# design.net
KiCad netlist of a schematic drawn in Altium Designer
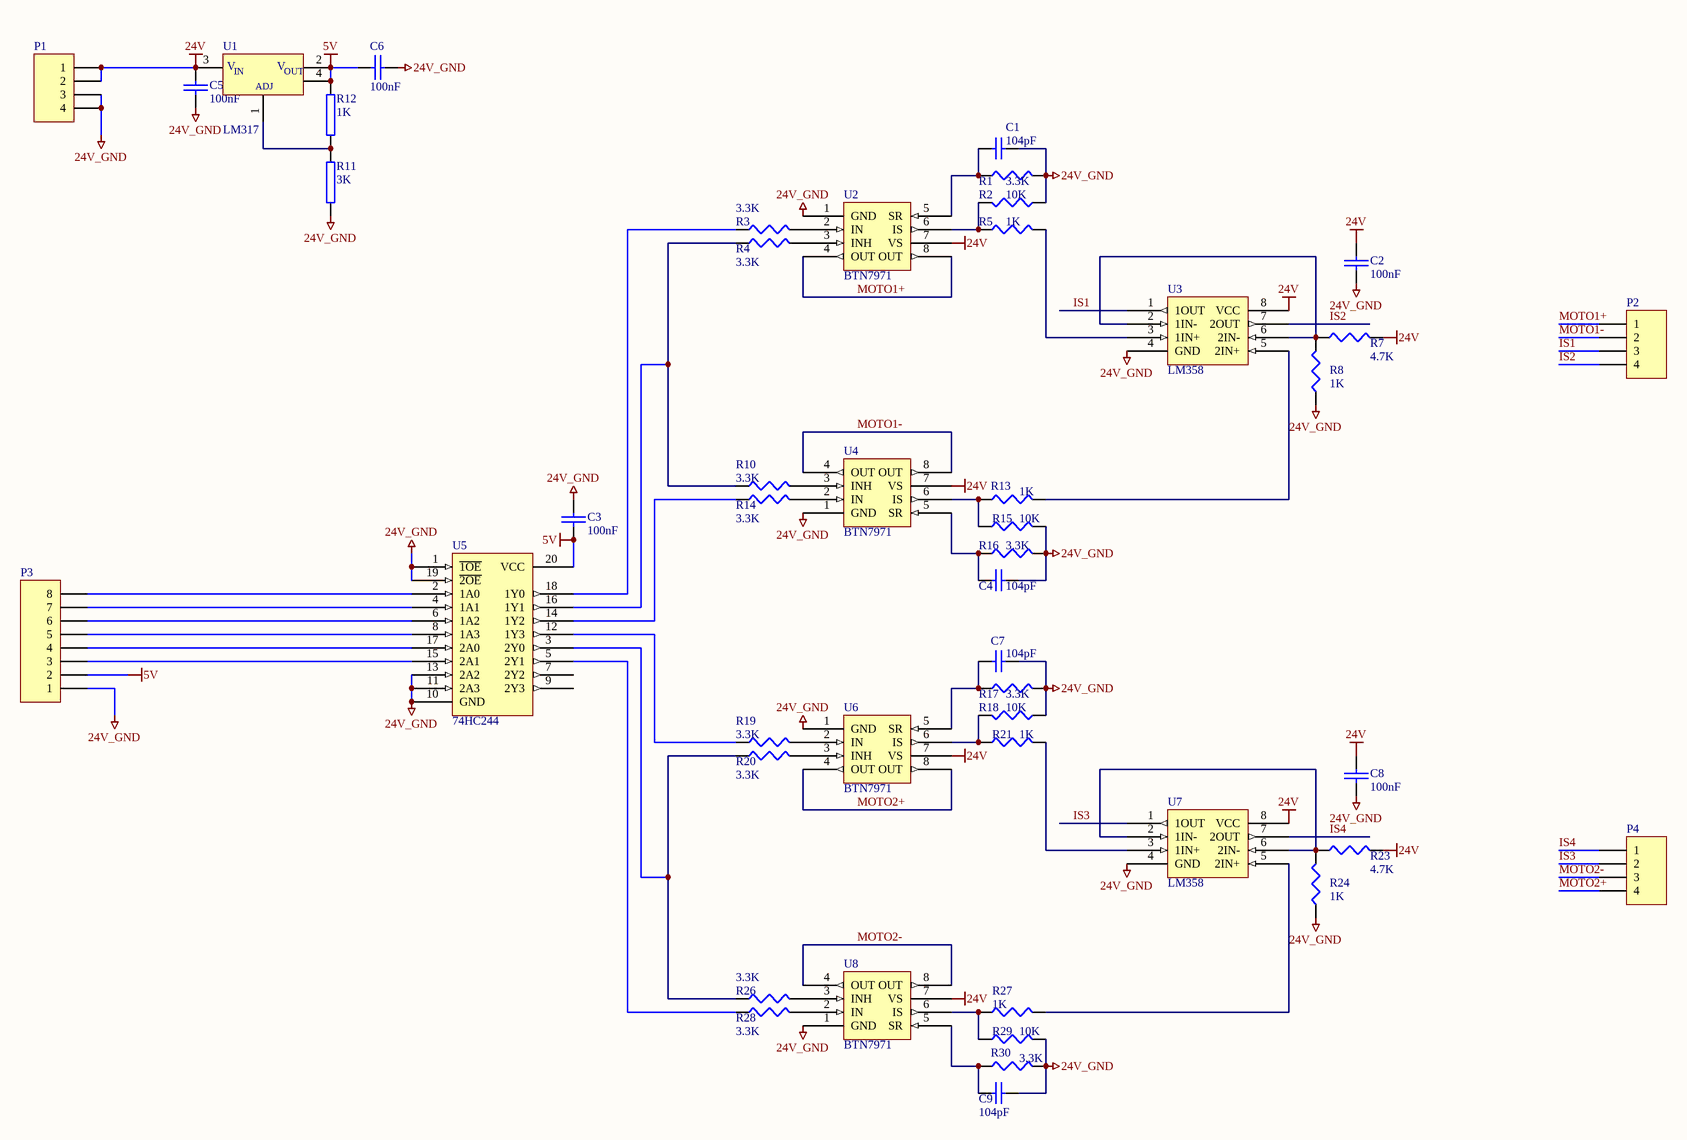
[diagram p0: 双电机电机模块.SchDoc]

(export (version "E")
  (design (tool "Eeschema 10.0.6"))
  (components
    (comp (ref "C1")
      (value "104pF")
      (footprint "0603c")
      (description "Capacitor (Semiconductor SIM Model)")
      (fields (field (name "Comment") "Cap Semi") (field (name "PUBLISHER") "Altium Limited"))
      (libsource (lib "Miscellaneous Devices") (part "Cap Semi"))
    )
    (comp (ref "C2")
      (value "100nF")
      (footprint "0603C")
      (description "CAP")
      (libsource (lib "*") (part "CAP"))
    )
    (comp (ref "C3")
      (value "100nF")
      (footprint "0603C")
      (description "CAP")
      (libsource (lib "*") (part "CAP"))
    )
    (comp (ref "C4")
      (value "104pF")
      (footprint "0603c")
      (description "Capacitor (Semiconductor SIM Model)")
      (fields (field (name "Comment") "Cap Semi") (field (name "PUBLISHER") "Altium Limited"))
      (libsource (lib "Miscellaneous Devices") (part "Cap Semi"))
    )
    (comp (ref "C5")
      (value "100nF")
      (footprint "0603C")
      (description "CAP")
      (libsource (lib "*") (part "CAP"))
    )
    (comp (ref "C6")
      (value "100nF")
      (footprint "0603C")
      (description "CAP")
      (libsource (lib "*") (part "CAP"))
    )
    (comp (ref "C7")
      (value "104pF")
      (footprint "0603c")
      (description "Capacitor (Semiconductor SIM Model)")
      (fields (field (name "Comment") "Cap Semi") (field (name "PUBLISHER") "Altium Limited"))
      (libsource (lib "Miscellaneous Devices") (part "Cap Semi"))
    )
    (comp (ref "C8")
      (value "100nF")
      (footprint "0603C")
      (description "CAP")
      (libsource (lib "*") (part "CAP"))
    )
    (comp (ref "C9")
      (value "104pF")
      (footprint "0603c")
      (description "Capacitor (Semiconductor SIM Model)")
      (fields (field (name "Comment") "Cap Semi") (field (name "PUBLISHER") "Altium Limited"))
      (libsource (lib "Miscellaneous Devices") (part "Cap Semi"))
    )
    (comp (ref "P1")
      (value "~")
      (footprint "4ELPV-3.96")
      (description "Header, 4-Pin")
      (fields (field (name "PUBLISHER") "Altium Limited"))
      (libsource (lib "") (part "Header 4_1"))
    )
    (comp (ref "P2")
      (value "~")
      (footprint "4ELPV-3.96")
      (description "Header, 4-Pin")
      (fields (field (name "PUBLISHER") "Altium Limited"))
      (libsource (lib "Miscellaneous Connectors") (part "Header 4"))
    )
    (comp (ref "P3")
      (value "~")
      (footprint "HDR1X8")
      (description "Header, 8-Pin")
      (fields (field (name "PUBLISHER") "Altium Limited"))
      (libsource (lib "Miscellaneous Connectors") (part "Header 8"))
    )
    (comp (ref "P4")
      (value "~")
      (footprint "4ELPV-3.96")
      (description "Header, 4-Pin")
      (fields (field (name "PUBLISHER") "Altium Limited"))
      (libsource (lib "Miscellaneous Connectors") (part "Header 4"))
    )
    (comp (ref "R1")
      (value "3.3K")
      (footprint "0603R")
      (description "Resistor")
      (fields (field (name "Comment") "Res3") (field (name "PUBLISHER") "Altium Limited"))
      (libsource (lib "Miscellaneous Devices") (part "Res3"))
    )
    (comp (ref "R2")
      (value "10K")
      (footprint "0603R")
      (description "Resistor")
      (fields (field (name "Comment") "Res3") (field (name "PUBLISHER") "Altium Limited"))
      (libsource (lib "Miscellaneous Devices") (part "Res3"))
    )
    (comp (ref "R3")
      (value "3.3K")
      (footprint "0603R")
      (description "Resistor")
      (fields (field (name "Comment") "Res3") (field (name "PUBLISHER") "Altium Limited"))
      (libsource (lib "Miscellaneous Devices") (part "Res3"))
    )
    (comp (ref "R4")
      (value "3.3K")
      (footprint "0603R")
      (description "Resistor")
      (fields (field (name "Comment") "Res3") (field (name "PUBLISHER") "Altium Limited"))
      (libsource (lib "Miscellaneous Devices") (part "Res3"))
    )
    (comp (ref "R5")
      (value "1K")
      (footprint "0603R")
      (description "Resistor")
      (fields (field (name "Comment") "Res3") (field (name "PUBLISHER") "Altium Limited"))
      (libsource (lib "Miscellaneous Devices") (part "Res3"))
    )
    (comp (ref "R7")
      (value "4.7K")
      (footprint "0603R")
      (description "Resistor")
      (fields (field (name "Comment") "Res3") (field (name "PUBLISHER") "Altium Limited"))
      (libsource (lib "Miscellaneous Devices") (part "Res3"))
    )
    (comp (ref "R8")
      (value "1K")
      (footprint "0603R")
      (description "Resistor")
      (fields (field (name "Comment") "Res3") (field (name "PUBLISHER") "Altium Limited"))
      (libsource (lib "Miscellaneous Devices") (part "Res3"))
    )
    (comp (ref "R10")
      (value "3.3K")
      (footprint "0603R")
      (description "Resistor")
      (fields (field (name "Comment") "Res3") (field (name "PUBLISHER") "Altium Limited"))
      (libsource (lib "Miscellaneous Devices") (part "Res3"))
    )
    (comp (ref "R11") (value "3K") (footprint "0603R") (libsource (lib "*") (part "RES2")))
    (comp (ref "R12") (value "1K") (footprint "0603R") (libsource (lib "*") (part "RES2")))
    (comp (ref "R13")
      (value "1K")
      (footprint "0603R")
      (description "Resistor")
      (fields (field (name "Comment") "Res3") (field (name "PUBLISHER") "Altium Limited"))
      (libsource (lib "Miscellaneous Devices") (part "Res3"))
    )
    (comp (ref "R14")
      (value "3.3K")
      (footprint "0603R")
      (description "Resistor")
      (fields (field (name "Comment") "Res3") (field (name "PUBLISHER") "Altium Limited"))
      (libsource (lib "Miscellaneous Devices") (part "Res3"))
    )
    (comp (ref "R15")
      (value "10K")
      (footprint "0603R")
      (description "Resistor")
      (fields (field (name "Comment") "Res3") (field (name "PUBLISHER") "Altium Limited"))
      (libsource (lib "Miscellaneous Devices") (part "Res3"))
    )
    (comp (ref "R16")
      (value "3.3K")
      (footprint "0603R")
      (description "Resistor")
      (fields (field (name "Comment") "Res3") (field (name "PUBLISHER") "Altium Limited"))
      (libsource (lib "Miscellaneous Devices") (part "Res3"))
    )
    (comp (ref "R17")
      (value "3.3K")
      (footprint "0603R")
      (description "Resistor")
      (fields (field (name "Comment") "Res3") (field (name "PUBLISHER") "Altium Limited"))
      (libsource (lib "Miscellaneous Devices") (part "Res3"))
    )
    (comp (ref "R18")
      (value "10K")
      (footprint "0603R")
      (description "Resistor")
      (fields (field (name "Comment") "Res3") (field (name "PUBLISHER") "Altium Limited"))
      (libsource (lib "Miscellaneous Devices") (part "Res3"))
    )
    (comp (ref "R19")
      (value "3.3K")
      (footprint "0603R")
      (description "Resistor")
      (fields (field (name "Comment") "Res3") (field (name "PUBLISHER") "Altium Limited"))
      (libsource (lib "Miscellaneous Devices") (part "Res3"))
    )
    (comp (ref "R20")
      (value "3.3K")
      (footprint "0603R")
      (description "Resistor")
      (fields (field (name "Comment") "Res3") (field (name "PUBLISHER") "Altium Limited"))
      (libsource (lib "Miscellaneous Devices") (part "Res3"))
    )
    (comp (ref "R21")
      (value "1K")
      (footprint "0603R")
      (description "Resistor")
      (fields (field (name "Comment") "Res3") (field (name "PUBLISHER") "Altium Limited"))
      (libsource (lib "Miscellaneous Devices") (part "Res3"))
    )
    (comp (ref "R23")
      (value "4.7K")
      (footprint "0603R")
      (description "Resistor")
      (fields (field (name "Comment") "Res3") (field (name "PUBLISHER") "Altium Limited"))
      (libsource (lib "Miscellaneous Devices") (part "Res3"))
    )
    (comp (ref "R24")
      (value "1K")
      (footprint "0603R")
      (description "Resistor")
      (fields (field (name "Comment") "Res3") (field (name "PUBLISHER") "Altium Limited"))
      (libsource (lib "Miscellaneous Devices") (part "Res3"))
    )
    (comp (ref "R26")
      (value "3.3K")
      (footprint "0603R")
      (description "Resistor")
      (fields (field (name "Comment") "Res3") (field (name "PUBLISHER") "Altium Limited"))
      (libsource (lib "Miscellaneous Devices") (part "Res3"))
    )
    (comp (ref "R27")
      (value "1K")
      (footprint "0603R")
      (description "Resistor")
      (fields (field (name "Comment") "Res3") (field (name "PUBLISHER") "Altium Limited"))
      (libsource (lib "Miscellaneous Devices") (part "Res3"))
    )
    (comp (ref "R28")
      (value "3.3K")
      (footprint "0603R")
      (description "Resistor")
      (fields (field (name "Comment") "Res3") (field (name "PUBLISHER") "Altium Limited"))
      (libsource (lib "Miscellaneous Devices") (part "Res3"))
    )
    (comp (ref "R29")
      (value "10K")
      (footprint "0603R")
      (description "Resistor")
      (fields (field (name "Comment") "Res3") (field (name "PUBLISHER") "Altium Limited"))
      (libsource (lib "Miscellaneous Devices") (part "Res3"))
    )
    (comp (ref "R30")
      (value "3.3K")
      (footprint "0603R")
      (description "Resistor")
      (fields (field (name "Comment") "Res3") (field (name "PUBLISHER") "Altium Limited"))
      (libsource (lib "Miscellaneous Devices") (part "Res3"))
    )
    (comp (ref "U1")
      (value "LM317")
      (footprint "sot223")
      (description "3-Terminal Adjustable Positive Voltage Regulator")
      (libsource (lib "Sheet2") (part "LM317"))
    )
    (comp (ref "U2") (value "BTN7971") (footprint "TO263-7-1") (libsource (lib "") (part "BTN7971_1")))
    (comp (ref "U3") (value "LM358") (footprint "SO-8") (libsource (lib "Sheet2") (part "LM358")))
    (comp (ref "U4") (value "BTN7971") (footprint "TO263-7-1") (libsource (lib "Sheet2") (part "BTN7971")))
    (comp (ref "U5") (value "74HC244") (footprint "SOIC20") (libsource (lib "lg") (part "74HC244")))
    (comp (ref "U6") (value "BTN7971") (footprint "TO263-7-1") (libsource (lib "") (part "BTN7971_1")))
    (comp (ref "U7") (value "LM358") (footprint "SO-8") (libsource (lib "Sheet2") (part "LM358")))
    (comp (ref "U8") (value "BTN7971") (footprint "TO263-7-1") (libsource (lib "Sheet2") (part "BTN7971")))
  )
  (nets
    (net (code "1") (name "/IS1") (class "Default")
      (node (ref "P2") (pin "3") (pinfunction "3_3") (pintype "passive"))
      (node (ref "U3") (pin "1") (pinfunction "1OUT_1") (pintype "output"))
    )
    (net (code "2") (name "/IS2") (class "Default")
      (node (ref "P2") (pin "4") (pinfunction "4_4") (pintype "passive"))
      (node (ref "U3") (pin "7") (pinfunction "2OUT_7") (pintype "output"))
    )
    (net (code "3") (name "/IS3") (class "Default")
      (node (ref "P4") (pin "2") (pinfunction "2_2") (pintype "passive"))
      (node (ref "U7") (pin "1") (pinfunction "1OUT_1") (pintype "output"))
    )
    (net (code "4") (name "/IS4") (class "Default")
      (node (ref "P4") (pin "1") (pinfunction "1_1") (pintype "passive"))
      (node (ref "U7") (pin "7") (pinfunction "2OUT_7") (pintype "output"))
    )
    (net (code "5") (name "/MOTO1+") (class "Default")
      (node (ref "P2") (pin "1") (pinfunction "1_1") (pintype "passive"))
      (node (ref "U2") (pin "4") (pinfunction "OUT_4") (pintype "output"))
      (node (ref "U2") (pin "8") (pinfunction "OUT_8") (pintype "output"))
    )
    (net (code "6") (name "/MOTO1-") (class "Default")
      (node (ref "P2") (pin "2") (pinfunction "2_2") (pintype "passive"))
      (node (ref "U4") (pin "4") (pinfunction "OUT_4") (pintype "output"))
      (node (ref "U4") (pin "8") (pinfunction "OUT_8") (pintype "output"))
    )
    (net (code "7") (name "/MOTO2+") (class "Default")
      (node (ref "P4") (pin "4") (pinfunction "4_4") (pintype "passive"))
      (node (ref "U6") (pin "4") (pinfunction "OUT_4") (pintype "output"))
      (node (ref "U6") (pin "8") (pinfunction "OUT_8") (pintype "output"))
    )
    (net (code "8") (name "/MOTO2-") (class "Default")
      (node (ref "P4") (pin "3") (pinfunction "3_3") (pintype "passive"))
      (node (ref "U8") (pin "4") (pinfunction "OUT_4") (pintype "output"))
      (node (ref "U8") (pin "8") (pinfunction "OUT_8") (pintype "output"))
    )
    (net (code "9") (name "5V") (class "Default")
      (node (ref "C3") (pin "1") (pintype "passive"))
      (node (ref "C6") (pin "2") (pintype "passive"))
      (node (ref "P3") (pin "2") (pinfunction "2_2") (pintype "passive"))
      (node (ref "R12") (pin "1") (pintype "passive"))
      (node (ref "U1") (pin "2") (pinfunction "VOUT_2") (pintype "passive"))
      (node (ref "U1") (pin "4") (pinfunction "VOUT_4") (pintype "passive"))
      (node (ref "U5") (pin "20") (pinfunction "VCC_20") (pintype "passive"))
    )
    (net (code "10") (name "24V") (class "Default")
      (node (ref "C2") (pin "2") (pintype "passive"))
      (node (ref "C5") (pin "1") (pintype "passive"))
      (node (ref "C8") (pin "2") (pintype "passive"))
      (node (ref "P1") (pin "1") (pinfunction "1_1") (pintype "passive"))
      (node (ref "P1") (pin "2") (pinfunction "2_2") (pintype "passive"))
      (node (ref "R23") (pin "2") (pinfunction "2_2") (pintype "passive"))
      (node (ref "R7") (pin "2") (pinfunction "2_2") (pintype "passive"))
      (node (ref "U1") (pin "3") (pinfunction "VIN_3") (pintype "passive"))
      (node (ref "U2") (pin "7") (pinfunction "VS_7") (pintype "passive"))
      (node (ref "U3") (pin "8") (pinfunction "VCC_8") (pintype "passive"))
      (node (ref "U4") (pin "7") (pinfunction "VS_7") (pintype "passive"))
      (node (ref "U6") (pin "7") (pinfunction "VS_7") (pintype "passive"))
      (node (ref "U7") (pin "8") (pinfunction "VCC_8") (pintype "passive"))
      (node (ref "U8") (pin "7") (pinfunction "VS_7") (pintype "passive"))
    )
    (net (code "11") (name "24V_GND") (class "Default")
      (node (ref "C1") (pin "2") (pinfunction "2_2") (pintype "passive"))
      (node (ref "C2") (pin "1") (pintype "passive"))
      (node (ref "C3") (pin "2") (pintype "passive"))
      (node (ref "C4") (pin "2") (pinfunction "2_2") (pintype "passive"))
      (node (ref "C5") (pin "2") (pintype "passive"))
      (node (ref "C6") (pin "1") (pintype "passive"))
      (node (ref "C7") (pin "2") (pinfunction "2_2") (pintype "passive"))
      (node (ref "C8") (pin "1") (pintype "passive"))
      (node (ref "C9") (pin "2") (pinfunction "2_2") (pintype "passive"))
      (node (ref "P1") (pin "3") (pinfunction "3_3") (pintype "passive"))
      (node (ref "P1") (pin "4") (pinfunction "4_4") (pintype "passive"))
      (node (ref "P3") (pin "1") (pinfunction "1_1") (pintype "passive"))
      (node (ref "R1") (pin "2") (pinfunction "2_2") (pintype "passive"))
      (node (ref "R11") (pin "1") (pintype "passive"))
      (node (ref "R15") (pin "2") (pinfunction "2_2") (pintype "passive"))
      (node (ref "R16") (pin "2") (pinfunction "2_2") (pintype "passive"))
      (node (ref "R17") (pin "2") (pinfunction "2_2") (pintype "passive"))
      (node (ref "R18") (pin "1") (pinfunction "1_1") (pintype "passive"))
      (node (ref "R2") (pin "1") (pinfunction "1_1") (pintype "passive"))
      (node (ref "R24") (pin "1") (pinfunction "1_1") (pintype "passive"))
      (node (ref "R29") (pin "2") (pinfunction "2_2") (pintype "passive"))
      (node (ref "R30") (pin "2") (pinfunction "2_2") (pintype "passive"))
      (node (ref "R8") (pin "1") (pinfunction "1_1") (pintype "passive"))
      (node (ref "U2") (pin "1") (pinfunction "GND_1") (pintype "passive"))
      (node (ref "U3") (pin "4") (pinfunction "GND_4") (pintype "passive"))
      (node (ref "U4") (pin "1") (pinfunction "GND_1") (pintype "passive"))
      (node (ref "U5") (pin "1") (pinfunction "~{1OE}_1") (pintype "input"))
      (node (ref "U5") (pin "10") (pinfunction "GND_10") (pintype "passive"))
      (node (ref "U5") (pin "11") (pinfunction "2A3_11") (pintype "input"))
      (node (ref "U5") (pin "13") (pinfunction "2A2_13") (pintype "input"))
      (node (ref "U5") (pin "19") (pinfunction "~{2OE}_19") (pintype "input"))
      (node (ref "U6") (pin "1") (pinfunction "GND_1") (pintype "passive"))
      (node (ref "U7") (pin "4") (pinfunction "GND_4") (pintype "passive"))
      (node (ref "U8") (pin "1") (pinfunction "GND_1") (pintype "passive"))
    )
    (net (code "12") (name "Net-(U1-ADJ)") (class "Default")
      (node (ref "R11") (pin "2") (pintype "passive"))
      (node (ref "R12") (pin "2") (pintype "passive"))
      (node (ref "U1") (pin "1") (pinfunction "ADJ_1") (pintype "passive"))
    )
    (net (code "13") (name "Net-(U2-IN)") (class "Default")
      (node (ref "R3") (pin "2") (pinfunction "2_2") (pintype "passive"))
      (node (ref "U2") (pin "2") (pinfunction "IN_2") (pintype "input"))
    )
    (net (code "14") (name "Net-(U2-INH)") (class "Default")
      (node (ref "R4") (pin "2") (pinfunction "2_2") (pintype "passive"))
      (node (ref "U2") (pin "3") (pinfunction "INH_3") (pintype "input"))
    )
    (net (code "15") (name "Net-(U2-IS)") (class "Default")
      (node (ref "R2") (pin "2") (pinfunction "2_2") (pintype "passive"))
      (node (ref "R5") (pin "1") (pinfunction "1_1") (pintype "passive"))
      (node (ref "U2") (pin "6") (pinfunction "IS_6") (pintype "output"))
    )
    (net (code "16") (name "Net-(U2-SR)") (class "Default")
      (node (ref "C1") (pin "1") (pinfunction "1_1") (pintype "passive"))
      (node (ref "R1") (pin "1") (pinfunction "1_1") (pintype "passive"))
      (node (ref "U2") (pin "5") (pinfunction "SR_5") (pintype "input"))
    )
    (net (code "17") (name "Net-(U3-1IN+)") (class "Default")
      (node (ref "R5") (pin "2") (pinfunction "2_2") (pintype "passive"))
      (node (ref "U3") (pin "3") (pinfunction "1IN+_3") (pintype "input"))
    )
    (net (code "18") (name "Net-(U3-1IN-)") (class "Default")
      (node (ref "R7") (pin "1") (pinfunction "1_1") (pintype "passive"))
      (node (ref "R8") (pin "2") (pinfunction "2_2") (pintype "passive"))
      (node (ref "U3") (pin "2") (pinfunction "1IN-_2") (pintype "input"))
      (node (ref "U3") (pin "6") (pinfunction "2IN-_6") (pintype "input"))
    )
    (net (code "19") (name "Net-(U3-2IN+)") (class "Default")
      (node (ref "R13") (pin "2") (pinfunction "2_2") (pintype "passive"))
      (node (ref "U3") (pin "5") (pinfunction "2IN+_5") (pintype "input"))
    )
    (net (code "20") (name "Net-(U4-IN)") (class "Default")
      (node (ref "R14") (pin "2") (pinfunction "2_2") (pintype "passive"))
      (node (ref "U4") (pin "2") (pinfunction "IN_2") (pintype "input"))
    )
    (net (code "21") (name "Net-(U4-INH)") (class "Default")
      (node (ref "R10") (pin "2") (pinfunction "2_2") (pintype "passive"))
      (node (ref "U4") (pin "3") (pinfunction "INH_3") (pintype "input"))
    )
    (net (code "22") (name "Net-(U4-IS)") (class "Default")
      (node (ref "R13") (pin "1") (pinfunction "1_1") (pintype "passive"))
      (node (ref "R15") (pin "1") (pinfunction "1_1") (pintype "passive"))
      (node (ref "U4") (pin "6") (pinfunction "IS_6") (pintype "output"))
    )
    (net (code "23") (name "Net-(U4-SR)") (class "Default")
      (node (ref "C4") (pin "1") (pinfunction "1_1") (pintype "passive"))
      (node (ref "R16") (pin "1") (pinfunction "1_1") (pintype "passive"))
      (node (ref "U4") (pin "5") (pinfunction "SR_5") (pintype "input"))
    )
    (net (code "24") (name "Net-(U5-1A0)") (class "Default")
      (node (ref "P3") (pin "8") (pinfunction "8_8") (pintype "passive"))
      (node (ref "U5") (pin "2") (pinfunction "1A0_2") (pintype "input"))
    )
    (net (code "25") (name "Net-(U5-1A1)") (class "Default")
      (node (ref "P3") (pin "7") (pinfunction "7_7") (pintype "passive"))
      (node (ref "U5") (pin "4") (pinfunction "1A1_4") (pintype "input"))
    )
    (net (code "26") (name "Net-(U5-1A2)") (class "Default")
      (node (ref "P3") (pin "6") (pinfunction "6_6") (pintype "passive"))
      (node (ref "U5") (pin "6") (pinfunction "1A2_6") (pintype "input"))
    )
    (net (code "27") (name "Net-(U5-1A3)") (class "Default")
      (node (ref "P3") (pin "5") (pinfunction "5_5") (pintype "passive"))
      (node (ref "U5") (pin "8") (pinfunction "1A3_8") (pintype "input"))
    )
    (net (code "28") (name "Net-(U5-1Y0)") (class "Default")
      (node (ref "R3") (pin "1") (pinfunction "1_1") (pintype "passive"))
      (node (ref "U5") (pin "18") (pinfunction "1Y0_18") (pintype "output"))
    )
    (net (code "29") (name "Net-(U5-1Y1)") (class "Default")
      (node (ref "R10") (pin "1") (pinfunction "1_1") (pintype "passive"))
      (node (ref "R4") (pin "1") (pinfunction "1_1") (pintype "passive"))
      (node (ref "U5") (pin "16") (pinfunction "1Y1_16") (pintype "output"))
    )
    (net (code "30") (name "Net-(U5-1Y2)") (class "Default")
      (node (ref "R14") (pin "1") (pinfunction "1_1") (pintype "passive"))
      (node (ref "U5") (pin "14") (pinfunction "1Y2_14") (pintype "output"))
    )
    (net (code "31") (name "Net-(U5-1Y3)") (class "Default")
      (node (ref "R19") (pin "1") (pinfunction "1_1") (pintype "passive"))
      (node (ref "U5") (pin "12") (pinfunction "1Y3_12") (pintype "output"))
    )
    (net (code "32") (name "Net-(U5-2A0)") (class "Default")
      (node (ref "P3") (pin "4") (pinfunction "4_4") (pintype "passive"))
      (node (ref "U5") (pin "17") (pinfunction "2A0_17") (pintype "input"))
    )
    (net (code "33") (name "Net-(U5-2A1)") (class "Default")
      (node (ref "P3") (pin "3") (pinfunction "3_3") (pintype "passive"))
      (node (ref "U5") (pin "15") (pinfunction "2A1_15") (pintype "input"))
    )
    (net (code "34") (name "Net-(U5-2Y0)") (class "Default")
      (node (ref "R20") (pin "1") (pinfunction "1_1") (pintype "passive"))
      (node (ref "R26") (pin "1") (pinfunction "1_1") (pintype "passive"))
      (node (ref "U5") (pin "3") (pinfunction "2Y0_3") (pintype "output"))
    )
    (net (code "35") (name "Net-(U5-2Y1)") (class "Default")
      (node (ref "R28") (pin "1") (pinfunction "1_1") (pintype "passive"))
      (node (ref "U5") (pin "5") (pinfunction "2Y1_5") (pintype "output"))
    )
    (net (code "36") (name "Net-(U6-IN)") (class "Default")
      (node (ref "R19") (pin "2") (pinfunction "2_2") (pintype "passive"))
      (node (ref "U6") (pin "2") (pinfunction "IN_2") (pintype "input"))
    )
    (net (code "37") (name "Net-(U6-INH)") (class "Default")
      (node (ref "R20") (pin "2") (pinfunction "2_2") (pintype "passive"))
      (node (ref "U6") (pin "3") (pinfunction "INH_3") (pintype "input"))
    )
    (net (code "38") (name "Net-(U6-IS)") (class "Default")
      (node (ref "R18") (pin "2") (pinfunction "2_2") (pintype "passive"))
      (node (ref "R21") (pin "1") (pinfunction "1_1") (pintype "passive"))
      (node (ref "U6") (pin "6") (pinfunction "IS_6") (pintype "output"))
    )
    (net (code "39") (name "Net-(U6-SR)") (class "Default")
      (node (ref "C7") (pin "1") (pinfunction "1_1") (pintype "passive"))
      (node (ref "R17") (pin "1") (pinfunction "1_1") (pintype "passive"))
      (node (ref "U6") (pin "5") (pinfunction "SR_5") (pintype "input"))
    )
    (net (code "40") (name "Net-(U7-1IN+)") (class "Default")
      (node (ref "R21") (pin "2") (pinfunction "2_2") (pintype "passive"))
      (node (ref "U7") (pin "3") (pinfunction "1IN+_3") (pintype "input"))
    )
    (net (code "41") (name "Net-(U7-1IN-)") (class "Default")
      (node (ref "R23") (pin "1") (pinfunction "1_1") (pintype "passive"))
      (node (ref "R24") (pin "2") (pinfunction "2_2") (pintype "passive"))
      (node (ref "U7") (pin "2") (pinfunction "1IN-_2") (pintype "input"))
      (node (ref "U7") (pin "6") (pinfunction "2IN-_6") (pintype "input"))
    )
    (net (code "42") (name "Net-(U7-2IN+)") (class "Default")
      (node (ref "R27") (pin "2") (pinfunction "2_2") (pintype "passive"))
      (node (ref "U7") (pin "5") (pinfunction "2IN+_5") (pintype "input"))
    )
    (net (code "43") (name "Net-(U8-IN)") (class "Default")
      (node (ref "R28") (pin "2") (pinfunction "2_2") (pintype "passive"))
      (node (ref "U8") (pin "2") (pinfunction "IN_2") (pintype "input"))
    )
    (net (code "44") (name "Net-(U8-INH)") (class "Default")
      (node (ref "R26") (pin "2") (pinfunction "2_2") (pintype "passive"))
      (node (ref "U8") (pin "3") (pinfunction "INH_3") (pintype "input"))
    )
    (net (code "45") (name "Net-(U8-IS)") (class "Default")
      (node (ref "R27") (pin "1") (pinfunction "1_1") (pintype "passive"))
      (node (ref "R29") (pin "1") (pinfunction "1_1") (pintype "passive"))
      (node (ref "U8") (pin "6") (pinfunction "IS_6") (pintype "output"))
    )
    (net (code "46") (name "Net-(U8-SR)") (class "Default")
      (node (ref "C9") (pin "1") (pinfunction "1_1") (pintype "passive"))
      (node (ref "R30") (pin "1") (pinfunction "1_1") (pintype "passive"))
      (node (ref "U8") (pin "5") (pinfunction "SR_5") (pintype "input"))
    )
    (net (code "47") (name "unconnected-(U5-2Y2-Pad7)") (class "Default")
      (node (ref "U5") (pin "7") (pinfunction "2Y2_7") (pintype "output"))
    )
    (net (code "48") (name "unconnected-(U5-2Y3-Pad9)") (class "Default")
      (node (ref "U5") (pin "9") (pinfunction "2Y3_9") (pintype "output"))
    )
  )
)
